# PGTN_daisy1_controls_8cvin_2cvout.net
KiCad netlist of a schematic drawn in EAGLE
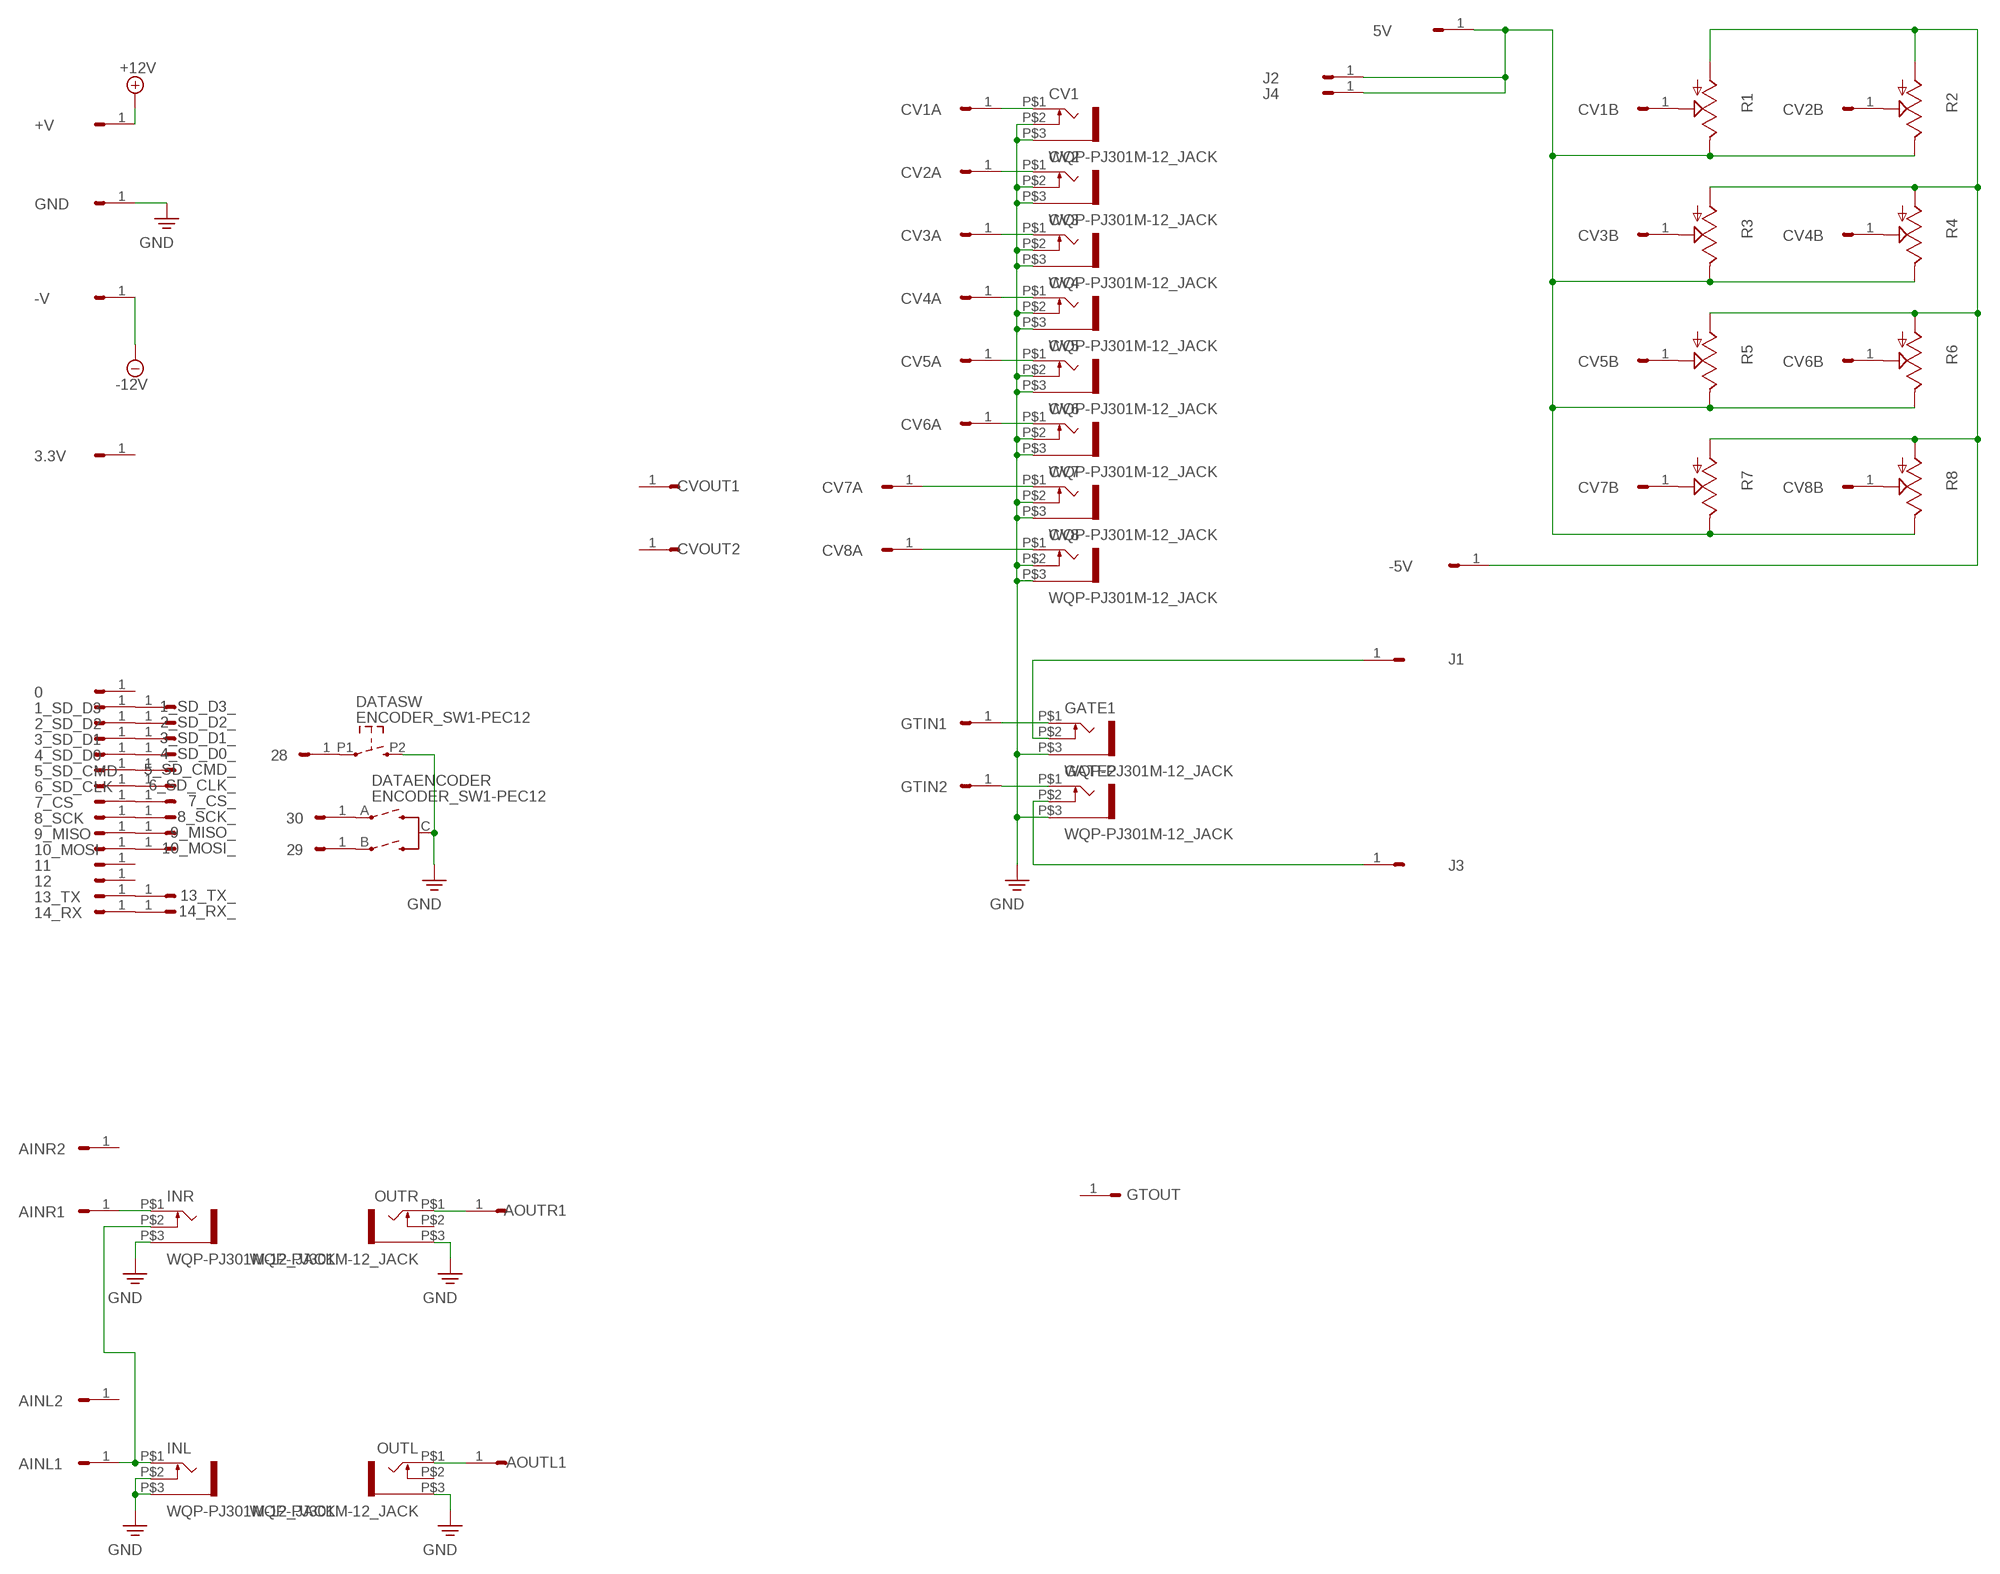
[diagram p0: schematic, sheet 1]

(export (version "E")
  (design (tool "Eeschema 10.0.6"))
  (components
    (comp (ref "+V")
      (value "HEADER/MALE/01")
      (footprint "eagle-import:HEADER_MALE_01")
      (fields (field (name "SPICEPREFIX") "X"))
      (libsource (lib "eagle-import") (part "HEADER/MALE/01"))
    )
    (comp (ref "-5V")
      (value "HEADER/MALE/01")
      (footprint "eagle-import:HEADER_MALE_01")
      (fields (field (name "SPICEPREFIX") "X"))
      (libsource (lib "eagle-import") (part "HEADER/MALE/01"))
    )
    (comp (ref "-V")
      (value "HEADER/MALE/01")
      (footprint "eagle-import:HEADER_MALE_01")
      (fields (field (name "SPICEPREFIX") "X"))
      (libsource (lib "eagle-import") (part "HEADER/MALE/01"))
    )
    (comp (ref "0")
      (value "HEADER/MALE/01")
      (footprint "eagle-import:HEADER_MALE_01")
      (fields (field (name "SPICEPREFIX") "X"))
      (libsource (lib "eagle-import") (part "HEADER/MALE/01"))
    )
    (comp (ref "1_SD_D3")
      (value "HEADER/MALE/01")
      (footprint "eagle-import:HEADER_MALE_01")
      (fields (field (name "SPICEPREFIX") "X"))
      (libsource (lib "eagle-import") (part "HEADER/MALE/01"))
    )
    (comp (ref "1_SD_D3_")
      (value "HEADER/MALE/01")
      (footprint "eagle-import:HEADER_MALE_01")
      (fields (field (name "SPICEPREFIX") "X"))
      (libsource (lib "eagle-import") (part "HEADER/MALE/01"))
    )
    (comp (ref "2_SD_D2")
      (value "HEADER/MALE/01")
      (footprint "eagle-import:HEADER_MALE_01")
      (fields (field (name "SPICEPREFIX") "X"))
      (libsource (lib "eagle-import") (part "HEADER/MALE/01"))
    )
    (comp (ref "2_SD_D2_")
      (value "HEADER/MALE/01")
      (footprint "eagle-import:HEADER_MALE_01")
      (fields (field (name "SPICEPREFIX") "X"))
      (libsource (lib "eagle-import") (part "HEADER/MALE/01"))
    )
    (comp (ref "3.3V")
      (value "HEADER/MALE/01")
      (footprint "eagle-import:HEADER_MALE_01")
      (fields (field (name "SPICEPREFIX") "X"))
      (libsource (lib "eagle-import") (part "HEADER/MALE/01"))
    )
    (comp (ref "3_SD_D1")
      (value "HEADER/MALE/01")
      (footprint "eagle-import:HEADER_MALE_01")
      (fields (field (name "SPICEPREFIX") "X"))
      (libsource (lib "eagle-import") (part "HEADER/MALE/01"))
    )
    (comp (ref "3_SD_D1_")
      (value "HEADER/MALE/01")
      (footprint "eagle-import:HEADER_MALE_01")
      (fields (field (name "SPICEPREFIX") "X"))
      (libsource (lib "eagle-import") (part "HEADER/MALE/01"))
    )
    (comp (ref "4_SD_D0")
      (value "HEADER/MALE/01")
      (footprint "eagle-import:HEADER_MALE_01")
      (fields (field (name "SPICEPREFIX") "X"))
      (libsource (lib "eagle-import") (part "HEADER/MALE/01"))
    )
    (comp (ref "4_SD_D0_")
      (value "HEADER/MALE/01")
      (footprint "eagle-import:HEADER_MALE_01")
      (fields (field (name "SPICEPREFIX") "X"))
      (libsource (lib "eagle-import") (part "HEADER/MALE/01"))
    )
    (comp (ref "5V")
      (value "HEADER/MALE/01")
      (footprint "eagle-import:HEADER_MALE_01")
      (fields (field (name "SPICEPREFIX") "X"))
      (libsource (lib "eagle-import") (part "HEADER/MALE/01"))
    )
    (comp (ref "5_SD_CMD")
      (value "HEADER/MALE/01")
      (footprint "eagle-import:HEADER_MALE_01")
      (fields (field (name "SPICEPREFIX") "X"))
      (libsource (lib "eagle-import") (part "HEADER/MALE/01"))
    )
    (comp (ref "5_SD_CMD_")
      (value "HEADER/MALE/01")
      (footprint "eagle-import:HEADER_MALE_01")
      (fields (field (name "SPICEPREFIX") "X"))
      (libsource (lib "eagle-import") (part "HEADER/MALE/01"))
    )
    (comp (ref "6_SD_CLK")
      (value "HEADER/MALE/01")
      (footprint "eagle-import:HEADER_MALE_01")
      (fields (field (name "SPICEPREFIX") "X"))
      (libsource (lib "eagle-import") (part "HEADER/MALE/01"))
    )
    (comp (ref "6_SD_CLK_")
      (value "HEADER/MALE/01")
      (footprint "eagle-import:HEADER_MALE_01")
      (fields (field (name "SPICEPREFIX") "X"))
      (libsource (lib "eagle-import") (part "HEADER/MALE/01"))
    )
    (comp (ref "7_CS")
      (value "HEADER/MALE/01")
      (footprint "eagle-import:HEADER_MALE_01")
      (fields (field (name "SPICEPREFIX") "X"))
      (libsource (lib "eagle-import") (part "HEADER/MALE/01"))
    )
    (comp (ref "7_CS_")
      (value "HEADER/MALE/01")
      (footprint "eagle-import:HEADER_MALE_01")
      (fields (field (name "SPICEPREFIX") "X"))
      (libsource (lib "eagle-import") (part "HEADER/MALE/01"))
    )
    (comp (ref "8_SCK")
      (value "HEADER/MALE/01")
      (footprint "eagle-import:HEADER_MALE_01")
      (fields (field (name "SPICEPREFIX") "X"))
      (libsource (lib "eagle-import") (part "HEADER/MALE/01"))
    )
    (comp (ref "8_SCK_")
      (value "HEADER/MALE/01")
      (footprint "eagle-import:HEADER_MALE_01")
      (fields (field (name "SPICEPREFIX") "X"))
      (libsource (lib "eagle-import") (part "HEADER/MALE/01"))
    )
    (comp (ref "9_MISO")
      (value "HEADER/MALE/01")
      (footprint "eagle-import:HEADER_MALE_01")
      (fields (field (name "SPICEPREFIX") "X"))
      (libsource (lib "eagle-import") (part "HEADER/MALE/01"))
    )
    (comp (ref "9_MISO_")
      (value "HEADER/MALE/01")
      (footprint "eagle-import:HEADER_MALE_01")
      (fields (field (name "SPICEPREFIX") "X"))
      (libsource (lib "eagle-import") (part "HEADER/MALE/01"))
    )
    (comp (ref "10_MOSI")
      (value "HEADER/MALE/01")
      (footprint "eagle-import:HEADER_MALE_01")
      (fields (field (name "SPICEPREFIX") "X"))
      (libsource (lib "eagle-import") (part "HEADER/MALE/01"))
    )
    (comp (ref "10_MOSI_")
      (value "HEADER/MALE/01")
      (footprint "eagle-import:HEADER_MALE_01")
      (fields (field (name "SPICEPREFIX") "X"))
      (libsource (lib "eagle-import") (part "HEADER/MALE/01"))
    )
    (comp (ref "11")
      (value "HEADER/MALE/01")
      (footprint "eagle-import:HEADER_MALE_01")
      (fields (field (name "SPICEPREFIX") "X"))
      (libsource (lib "eagle-import") (part "HEADER/MALE/01"))
    )
    (comp (ref "12")
      (value "HEADER/MALE/01")
      (footprint "eagle-import:HEADER_MALE_01")
      (fields (field (name "SPICEPREFIX") "X"))
      (libsource (lib "eagle-import") (part "HEADER/MALE/01"))
    )
    (comp (ref "13_TX")
      (value "HEADER/MALE/01")
      (footprint "eagle-import:HEADER_MALE_01")
      (fields (field (name "SPICEPREFIX") "X"))
      (libsource (lib "eagle-import") (part "HEADER/MALE/01"))
    )
    (comp (ref "13_TX_")
      (value "HEADER/MALE/01")
      (footprint "eagle-import:HEADER_MALE_01")
      (fields (field (name "SPICEPREFIX") "X"))
      (libsource (lib "eagle-import") (part "HEADER/MALE/01"))
    )
    (comp (ref "14_RX")
      (value "HEADER/MALE/01")
      (footprint "eagle-import:HEADER_MALE_01")
      (fields (field (name "SPICEPREFIX") "X"))
      (libsource (lib "eagle-import") (part "HEADER/MALE/01"))
    )
    (comp (ref "14_RX_")
      (value "HEADER/MALE/01")
      (footprint "eagle-import:HEADER_MALE_01")
      (fields (field (name "SPICEPREFIX") "X"))
      (libsource (lib "eagle-import") (part "HEADER/MALE/01"))
    )
    (comp (ref "28")
      (value "HEADER/MALE/01")
      (footprint "eagle-import:HEADER_MALE_01")
      (fields (field (name "SPICEPREFIX") "X"))
      (libsource (lib "eagle-import") (part "HEADER/MALE/01"))
    )
    (comp (ref "29")
      (value "HEADER/MALE/01")
      (footprint "eagle-import:HEADER_MALE_01")
      (fields (field (name "SPICEPREFIX") "X"))
      (libsource (lib "eagle-import") (part "HEADER/MALE/01"))
    )
    (comp (ref "30")
      (value "HEADER/MALE/01")
      (footprint "eagle-import:HEADER_MALE_01")
      (fields (field (name "SPICEPREFIX") "X"))
      (libsource (lib "eagle-import") (part "HEADER/MALE/01"))
    )
    (comp (ref "AINL1")
      (value "HEADER/MALE/01")
      (footprint "eagle-import:HEADER_MALE_01")
      (fields (field (name "SPICEPREFIX") "X"))
      (libsource (lib "eagle-import") (part "HEADER/MALE/01"))
    )
    (comp (ref "AINL2")
      (value "HEADER/MALE/01")
      (footprint "eagle-import:HEADER_MALE_01")
      (fields (field (name "SPICEPREFIX") "X"))
      (libsource (lib "eagle-import") (part "HEADER/MALE/01"))
    )
    (comp (ref "AINR1")
      (value "HEADER/MALE/01")
      (footprint "eagle-import:HEADER_MALE_01")
      (fields (field (name "SPICEPREFIX") "X"))
      (libsource (lib "eagle-import") (part "HEADER/MALE/01"))
    )
    (comp (ref "AINR2")
      (value "HEADER/MALE/01")
      (footprint "eagle-import:HEADER_MALE_01")
      (fields (field (name "SPICEPREFIX") "X"))
      (libsource (lib "eagle-import") (part "HEADER/MALE/01"))
    )
    (comp (ref "AOUTL1")
      (value "HEADER/MALE/01")
      (footprint "eagle-import:HEADER_MALE_01")
      (fields (field (name "SPICEPREFIX") "X"))
      (libsource (lib "eagle-import") (part "HEADER/MALE/01"))
    )
    (comp (ref "AOUTR1")
      (value "HEADER/MALE/01")
      (footprint "eagle-import:HEADER_MALE_01")
      (fields (field (name "SPICEPREFIX") "X"))
      (libsource (lib "eagle-import") (part "HEADER/MALE/01"))
    )
    (comp (ref "CV1")
      (value "WQP-PJ301M-12_JACK")
      (footprint "eagle-import:WQP-PJ301M-12_JACK")
      (libsource (lib "eagle-import") (part "WQP-PJ301M-12_JACK"))
    )
    (comp (ref "CV1A")
      (value "HEADER/MALE/01")
      (footprint "eagle-import:HEADER_MALE_01")
      (fields (field (name "SPICEPREFIX") "X"))
      (libsource (lib "eagle-import") (part "HEADER/MALE/01"))
    )
    (comp (ref "CV1B")
      (value "HEADER/MALE/01")
      (footprint "eagle-import:HEADER_MALE_01")
      (fields (field (name "SPICEPREFIX") "X"))
      (libsource (lib "eagle-import") (part "HEADER/MALE/01"))
    )
    (comp (ref "CV2")
      (value "WQP-PJ301M-12_JACK")
      (footprint "eagle-import:WQP-PJ301M-12_JACK")
      (libsource (lib "eagle-import") (part "WQP-PJ301M-12_JACK"))
    )
    (comp (ref "CV2A")
      (value "HEADER/MALE/01")
      (footprint "eagle-import:HEADER_MALE_01")
      (fields (field (name "SPICEPREFIX") "X"))
      (libsource (lib "eagle-import") (part "HEADER/MALE/01"))
    )
    (comp (ref "CV2B")
      (value "HEADER/MALE/01")
      (footprint "eagle-import:HEADER_MALE_01")
      (fields (field (name "SPICEPREFIX") "X"))
      (libsource (lib "eagle-import") (part "HEADER/MALE/01"))
    )
    (comp (ref "CV3")
      (value "WQP-PJ301M-12_JACK")
      (footprint "eagle-import:WQP-PJ301M-12_JACK")
      (libsource (lib "eagle-import") (part "WQP-PJ301M-12_JACK"))
    )
    (comp (ref "CV3A")
      (value "HEADER/MALE/01")
      (footprint "eagle-import:HEADER_MALE_01")
      (fields (field (name "SPICEPREFIX") "X"))
      (libsource (lib "eagle-import") (part "HEADER/MALE/01"))
    )
    (comp (ref "CV3B")
      (value "HEADER/MALE/01")
      (footprint "eagle-import:HEADER_MALE_01")
      (fields (field (name "SPICEPREFIX") "X"))
      (libsource (lib "eagle-import") (part "HEADER/MALE/01"))
    )
    (comp (ref "CV4")
      (value "WQP-PJ301M-12_JACK")
      (footprint "eagle-import:WQP-PJ301M-12_JACK")
      (libsource (lib "eagle-import") (part "WQP-PJ301M-12_JACK"))
    )
    (comp (ref "CV4A")
      (value "HEADER/MALE/01")
      (footprint "eagle-import:HEADER_MALE_01")
      (fields (field (name "SPICEPREFIX") "X"))
      (libsource (lib "eagle-import") (part "HEADER/MALE/01"))
    )
    (comp (ref "CV4B")
      (value "HEADER/MALE/01")
      (footprint "eagle-import:HEADER_MALE_01")
      (fields (field (name "SPICEPREFIX") "X"))
      (libsource (lib "eagle-import") (part "HEADER/MALE/01"))
    )
    (comp (ref "CV5")
      (value "WQP-PJ301M-12_JACK")
      (footprint "eagle-import:WQP-PJ301M-12_JACK")
      (libsource (lib "eagle-import") (part "WQP-PJ301M-12_JACK"))
    )
    (comp (ref "CV5A")
      (value "HEADER/MALE/01")
      (footprint "eagle-import:HEADER_MALE_01")
      (fields (field (name "SPICEPREFIX") "X"))
      (libsource (lib "eagle-import") (part "HEADER/MALE/01"))
    )
    (comp (ref "CV5B")
      (value "HEADER/MALE/01")
      (footprint "eagle-import:HEADER_MALE_01")
      (fields (field (name "SPICEPREFIX") "X"))
      (libsource (lib "eagle-import") (part "HEADER/MALE/01"))
    )
    (comp (ref "CV6")
      (value "WQP-PJ301M-12_JACK")
      (footprint "eagle-import:WQP-PJ301M-12_JACK")
      (libsource (lib "eagle-import") (part "WQP-PJ301M-12_JACK"))
    )
    (comp (ref "CV6A")
      (value "HEADER/MALE/01")
      (footprint "eagle-import:HEADER_MALE_01")
      (fields (field (name "SPICEPREFIX") "X"))
      (libsource (lib "eagle-import") (part "HEADER/MALE/01"))
    )
    (comp (ref "CV6B")
      (value "HEADER/MALE/01")
      (footprint "eagle-import:HEADER_MALE_01")
      (fields (field (name "SPICEPREFIX") "X"))
      (libsource (lib "eagle-import") (part "HEADER/MALE/01"))
    )
    (comp (ref "CV7")
      (value "WQP-PJ301M-12_JACK")
      (footprint "eagle-import:WQP-PJ301M-12_JACK")
      (libsource (lib "eagle-import") (part "WQP-PJ301M-12_JACK"))
    )
    (comp (ref "CV7A")
      (value "HEADER/MALE/01")
      (footprint "eagle-import:HEADER_MALE_01")
      (fields (field (name "SPICEPREFIX") "X"))
      (libsource (lib "eagle-import") (part "HEADER/MALE/01"))
    )
    (comp (ref "CV7B")
      (value "HEADER/MALE/01")
      (footprint "eagle-import:HEADER_MALE_01")
      (fields (field (name "SPICEPREFIX") "X"))
      (libsource (lib "eagle-import") (part "HEADER/MALE/01"))
    )
    (comp (ref "CV8")
      (value "WQP-PJ301M-12_JACK")
      (footprint "eagle-import:WQP-PJ301M-12_JACK")
      (libsource (lib "eagle-import") (part "WQP-PJ301M-12_JACK"))
    )
    (comp (ref "CV8A")
      (value "HEADER/MALE/01")
      (footprint "eagle-import:HEADER_MALE_01")
      (fields (field (name "SPICEPREFIX") "X"))
      (libsource (lib "eagle-import") (part "HEADER/MALE/01"))
    )
    (comp (ref "CV8B")
      (value "HEADER/MALE/01")
      (footprint "eagle-import:HEADER_MALE_01")
      (fields (field (name "SPICEPREFIX") "X"))
      (libsource (lib "eagle-import") (part "HEADER/MALE/01"))
    )
    (comp (ref "CVOUT1")
      (value "HEADER/MALE/01")
      (footprint "eagle-import:HEADER_MALE_01")
      (fields (field (name "SPICEPREFIX") "X"))
      (libsource (lib "eagle-import") (part "HEADER/MALE/01"))
    )
    (comp (ref "CVOUT2")
      (value "HEADER/MALE/01")
      (footprint "eagle-import:HEADER_MALE_01")
      (fields (field (name "SPICEPREFIX") "X"))
      (libsource (lib "eagle-import") (part "HEADER/MALE/01"))
    )
    (comp (ref "DATA")
      (value "ENCODER_SW1-PEC12")
      (footprint "eagle-import:PEC12_INCREMENTAL_ENCODER")
      (libsource (lib "eagle-import") (part "ENCODER_SW1-PEC12"))
    )
    (comp (ref "GATE1")
      (value "WQP-PJ301M-12_JACK")
      (footprint "eagle-import:WQP-PJ301M-12_JACK")
      (libsource (lib "eagle-import") (part "WQP-PJ301M-12_JACK"))
    )
    (comp (ref "GATE2")
      (value "WQP-PJ301M-12_JACK")
      (footprint "eagle-import:WQP-PJ301M-12_JACK")
      (libsource (lib "eagle-import") (part "WQP-PJ301M-12_JACK"))
    )
    (comp (ref "GND")
      (value "HEADER/MALE/01")
      (footprint "eagle-import:HEADER_MALE_01")
      (fields (field (name "SPICEPREFIX") "X"))
      (libsource (lib "eagle-import") (part "HEADER/MALE/01"))
    )
    (comp (ref "GTIN1")
      (value "HEADER/MALE/01")
      (footprint "eagle-import:HEADER_MALE_01")
      (fields (field (name "SPICEPREFIX") "X"))
      (libsource (lib "eagle-import") (part "HEADER/MALE/01"))
    )
    (comp (ref "GTIN2")
      (value "HEADER/MALE/01")
      (footprint "eagle-import:HEADER_MALE_01")
      (fields (field (name "SPICEPREFIX") "X"))
      (libsource (lib "eagle-import") (part "HEADER/MALE/01"))
    )
    (comp (ref "GTOUT")
      (value "HEADER/MALE/01")
      (footprint "eagle-import:HEADER_MALE_01")
      (fields (field (name "SPICEPREFIX") "X"))
      (libsource (lib "eagle-import") (part "HEADER/MALE/01"))
    )
    (comp (ref "INL")
      (value "WQP-PJ301M-12_JACK")
      (footprint "eagle-import:WQP-PJ301M-12_JACK")
      (libsource (lib "eagle-import") (part "WQP-PJ301M-12_JACK"))
    )
    (comp (ref "INR")
      (value "WQP-PJ301M-12_JACK")
      (footprint "eagle-import:WQP-PJ301M-12_JACK")
      (libsource (lib "eagle-import") (part "WQP-PJ301M-12_JACK"))
    )
    (comp (ref "J1")
      (value "HEADER/MALE/01")
      (footprint "eagle-import:HEADER_MALE_01")
      (fields (field (name "SPICEPREFIX") "X"))
      (libsource (lib "eagle-import") (part "HEADER/MALE/01"))
    )
    (comp (ref "J2")
      (value "HEADER/MALE/01")
      (footprint "eagle-import:HEADER_MALE_01")
      (fields (field (name "SPICEPREFIX") "X"))
      (libsource (lib "eagle-import") (part "HEADER/MALE/01"))
    )
    (comp (ref "J3")
      (value "HEADER/MALE/01")
      (footprint "eagle-import:HEADER_MALE_01")
      (fields (field (name "SPICEPREFIX") "X"))
      (libsource (lib "eagle-import") (part "HEADER/MALE/01"))
    )
    (comp (ref "J4")
      (value "HEADER/MALE/01")
      (footprint "eagle-import:HEADER_MALE_01")
      (fields (field (name "SPICEPREFIX") "X"))
      (libsource (lib "eagle-import") (part "HEADER/MALE/01"))
    )
    (comp (ref "OUTL")
      (value "WQP-PJ301M-12_JACK")
      (footprint "eagle-import:WQP-PJ301M-12_JACK")
      (libsource (lib "eagle-import") (part "WQP-PJ301M-12_JACK"))
    )
    (comp (ref "OUTR")
      (value "WQP-PJ301M-12_JACK")
      (footprint "eagle-import:WQP-PJ301M-12_JACK")
      (libsource (lib "eagle-import") (part "WQP-PJ301M-12_JACK"))
    )
    (comp (ref "R1")
      (value "9MM_SNAP-IN_POT_")
      (footprint "eagle-import:9MM_SNAP-IN_POT")
      (libsource (lib "eagle-import") (part "9MM_SNAP-IN_POT_"))
    )
    (comp (ref "R2")
      (value "9MM_SNAP-IN_POT_")
      (footprint "eagle-import:9MM_SNAP-IN_POT")
      (libsource (lib "eagle-import") (part "9MM_SNAP-IN_POT_"))
    )
    (comp (ref "R3")
      (value "9MM_SNAP-IN_POT_")
      (footprint "eagle-import:9MM_SNAP-IN_POT")
      (libsource (lib "eagle-import") (part "9MM_SNAP-IN_POT_"))
    )
    (comp (ref "R4")
      (value "9MM_SNAP-IN_POT_")
      (footprint "eagle-import:9MM_SNAP-IN_POT")
      (libsource (lib "eagle-import") (part "9MM_SNAP-IN_POT_"))
    )
    (comp (ref "R5")
      (value "9MM_SNAP-IN_POT_")
      (footprint "eagle-import:9MM_SNAP-IN_POT")
      (libsource (lib "eagle-import") (part "9MM_SNAP-IN_POT_"))
    )
    (comp (ref "R6")
      (value "9MM_SNAP-IN_POT_")
      (footprint "eagle-import:9MM_SNAP-IN_POT")
      (libsource (lib "eagle-import") (part "9MM_SNAP-IN_POT_"))
    )
    (comp (ref "R7")
      (value "9MM_SNAP-IN_POT_")
      (footprint "eagle-import:9MM_SNAP-IN_POT")
      (libsource (lib "eagle-import") (part "9MM_SNAP-IN_POT_"))
    )
    (comp (ref "R8")
      (value "9MM_SNAP-IN_POT_")
      (footprint "eagle-import:9MM_SNAP-IN_POT")
      (libsource (lib "eagle-import") (part "9MM_SNAP-IN_POT_"))
    )
  )
  (nets
    (net (code "1") (name "+12V") (class "Default")
      (node (ref "+V") (pin "1") (pinfunction "3_1") (pintype "passive"))
    )
    (net (code "2") (name "-12V") (class "Default")
      (node (ref "-V") (pin "1") (pinfunction "3_1") (pintype "passive"))
    )
    (net (code "3") (name "GND") (class "Default")
      (node (ref "CV1") (pin "P$2") (pinfunction "3_P$2") (pintype "passive"))
      (node (ref "CV1") (pin "P$3") (pinfunction "1_P$3") (pintype "passive"))
      (node (ref "CV2") (pin "P$2") (pinfunction "3_P$2") (pintype "passive"))
      (node (ref "CV2") (pin "P$3") (pinfunction "1_P$3") (pintype "passive"))
      (node (ref "CV3") (pin "P$2") (pinfunction "3_P$2") (pintype "passive"))
      (node (ref "CV3") (pin "P$3") (pinfunction "1_P$3") (pintype "passive"))
      (node (ref "CV4") (pin "P$2") (pinfunction "3_P$2") (pintype "passive"))
      (node (ref "CV4") (pin "P$3") (pinfunction "1_P$3") (pintype "passive"))
      (node (ref "CV5") (pin "P$2") (pinfunction "3_P$2") (pintype "passive"))
      (node (ref "CV5") (pin "P$3") (pinfunction "1_P$3") (pintype "passive"))
      (node (ref "CV6") (pin "P$2") (pinfunction "3_P$2") (pintype "passive"))
      (node (ref "CV6") (pin "P$3") (pinfunction "1_P$3") (pintype "passive"))
      (node (ref "CV7") (pin "P$2") (pinfunction "3_P$2") (pintype "passive"))
      (node (ref "CV7") (pin "P$3") (pinfunction "1_P$3") (pintype "passive"))
      (node (ref "CV8") (pin "P$2") (pinfunction "3_P$2") (pintype "passive"))
      (node (ref "CV8") (pin "P$3") (pinfunction "1_P$3") (pintype "passive"))
      (node (ref "DATA") (pin "C") (pinfunction "C_C") (pintype "passive"))
      (node (ref "DATA") (pin "P2") (pinfunction "2_P2") (pintype "passive"))
      (node (ref "GATE1") (pin "P$3") (pinfunction "1_P$3") (pintype "passive"))
      (node (ref "GATE2") (pin "P$3") (pinfunction "1_P$3") (pintype "passive"))
      (node (ref "GND") (pin "1") (pinfunction "3_1") (pintype "passive"))
      (node (ref "INL") (pin "P$2") (pinfunction "3_P$2") (pintype "passive"))
      (node (ref "INL") (pin "P$3") (pinfunction "1_P$3") (pintype "passive"))
      (node (ref "INR") (pin "P$3") (pinfunction "1_P$3") (pintype "passive"))
      (node (ref "OUTL") (pin "P$3") (pinfunction "1_P$3") (pintype "passive"))
      (node (ref "OUTR") (pin "P$3") (pinfunction "1_P$3") (pintype "passive"))
    )
    (net (code "4") (name "Net-(-5V-3)") (class "Default")
      (node (ref "-5V") (pin "1") (pinfunction "3_1") (pintype "passive"))
      (node (ref "R1") (pin "1") (pinfunction "A_1") (pintype "passive"))
      (node (ref "R2") (pin "1") (pinfunction "A_1") (pintype "passive"))
      (node (ref "R3") (pin "1") (pinfunction "A_1") (pintype "passive"))
      (node (ref "R4") (pin "1") (pinfunction "A_1") (pintype "passive"))
      (node (ref "R5") (pin "1") (pinfunction "A_1") (pintype "passive"))
      (node (ref "R6") (pin "1") (pinfunction "A_1") (pintype "passive"))
      (node (ref "R7") (pin "1") (pinfunction "A_1") (pintype "passive"))
      (node (ref "R8") (pin "1") (pinfunction "A_1") (pintype "passive"))
    )
    (net (code "5") (name "Net-(1_SD_D3-3)") (class "Default")
      (node (ref "1_SD_D3") (pin "1") (pinfunction "3_1") (pintype "passive"))
      (node (ref "1_SD_D3_") (pin "1") (pinfunction "3_1") (pintype "passive"))
    )
    (net (code "6") (name "Net-(2_SD_D2-3)") (class "Default")
      (node (ref "2_SD_D2") (pin "1") (pinfunction "3_1") (pintype "passive"))
      (node (ref "2_SD_D2_") (pin "1") (pinfunction "3_1") (pintype "passive"))
    )
    (net (code "7") (name "Net-(3_SD_D1-3)") (class "Default")
      (node (ref "3_SD_D1") (pin "1") (pinfunction "3_1") (pintype "passive"))
      (node (ref "3_SD_D1_") (pin "1") (pinfunction "3_1") (pintype "passive"))
    )
    (net (code "8") (name "Net-(4_SD_D0-3)") (class "Default")
      (node (ref "4_SD_D0") (pin "1") (pinfunction "3_1") (pintype "passive"))
      (node (ref "4_SD_D0_") (pin "1") (pinfunction "3_1") (pintype "passive"))
    )
    (net (code "9") (name "Net-(5V-3)") (class "Default")
      (node (ref "5V") (pin "1") (pinfunction "3_1") (pintype "passive"))
      (node (ref "J2") (pin "1") (pinfunction "3_1") (pintype "passive"))
      (node (ref "J4") (pin "1") (pinfunction "3_1") (pintype "passive"))
      (node (ref "R1") (pin "3") (pinfunction "E_3") (pintype "passive"))
      (node (ref "R2") (pin "3") (pinfunction "E_3") (pintype "passive"))
      (node (ref "R3") (pin "3") (pinfunction "E_3") (pintype "passive"))
      (node (ref "R4") (pin "3") (pinfunction "E_3") (pintype "passive"))
      (node (ref "R5") (pin "3") (pinfunction "E_3") (pintype "passive"))
      (node (ref "R6") (pin "3") (pinfunction "E_3") (pintype "passive"))
      (node (ref "R7") (pin "3") (pinfunction "E_3") (pintype "passive"))
      (node (ref "R8") (pin "3") (pinfunction "E_3") (pintype "passive"))
    )
    (net (code "10") (name "Net-(5_SD_CMD-3)") (class "Default")
      (node (ref "5_SD_CMD") (pin "1") (pinfunction "3_1") (pintype "passive"))
      (node (ref "5_SD_CMD_") (pin "1") (pinfunction "3_1") (pintype "passive"))
    )
    (net (code "11") (name "Net-(6_SD_CLK-3)") (class "Default")
      (node (ref "6_SD_CLK") (pin "1") (pinfunction "3_1") (pintype "passive"))
      (node (ref "6_SD_CLK_") (pin "1") (pinfunction "3_1") (pintype "passive"))
    )
    (net (code "12") (name "Net-(7_CS-3)") (class "Default")
      (node (ref "7_CS") (pin "1") (pinfunction "3_1") (pintype "passive"))
      (node (ref "7_CS_") (pin "1") (pinfunction "3_1") (pintype "passive"))
    )
    (net (code "13") (name "Net-(8_SCK-3)") (class "Default")
      (node (ref "8_SCK") (pin "1") (pinfunction "3_1") (pintype "passive"))
      (node (ref "8_SCK_") (pin "1") (pinfunction "3_1") (pintype "passive"))
    )
    (net (code "14") (name "Net-(9_MISO-3)") (class "Default")
      (node (ref "9_MISO") (pin "1") (pinfunction "3_1") (pintype "passive"))
      (node (ref "9_MISO_") (pin "1") (pinfunction "3_1") (pintype "passive"))
    )
    (net (code "15") (name "Net-(10_MOSI-3)") (class "Default")
      (node (ref "10_MOSI") (pin "1") (pinfunction "3_1") (pintype "passive"))
      (node (ref "10_MOSI_") (pin "1") (pinfunction "3_1") (pintype "passive"))
    )
    (net (code "16") (name "Net-(13_TX-3)") (class "Default")
      (node (ref "13_TX") (pin "1") (pinfunction "3_1") (pintype "passive"))
      (node (ref "13_TX_") (pin "1") (pinfunction "3_1") (pintype "passive"))
    )
    (net (code "17") (name "Net-(14_RX-3)") (class "Default")
      (node (ref "14_RX") (pin "1") (pinfunction "3_1") (pintype "passive"))
      (node (ref "14_RX_") (pin "1") (pinfunction "3_1") (pintype "passive"))
    )
    (net (code "18") (name "Net-(28-3)") (class "Default")
      (node (ref "28") (pin "1") (pinfunction "3_1") (pintype "passive"))
      (node (ref "DATA") (pin "P1") (pinfunction "1_P1") (pintype "passive"))
    )
    (net (code "19") (name "Net-(29-3)") (class "Default")
      (node (ref "29") (pin "1") (pinfunction "3_1") (pintype "passive"))
      (node (ref "DATA") (pin "B") (pinfunction "B_B") (pintype "passive"))
    )
    (net (code "20") (name "Net-(30-3)") (class "Default")
      (node (ref "30") (pin "1") (pinfunction "3_1") (pintype "passive"))
      (node (ref "DATA") (pin "A") (pinfunction "A_A") (pintype "passive"))
    )
    (net (code "21") (name "Net-(AINL1-3)") (class "Default")
      (node (ref "AINL1") (pin "1") (pinfunction "3_1") (pintype "passive"))
      (node (ref "INL") (pin "P$1") (pinfunction "2_P$1") (pintype "passive"))
      (node (ref "INR") (pin "P$2") (pinfunction "3_P$2") (pintype "passive"))
    )
    (net (code "22") (name "Net-(AINR1-3)") (class "Default")
      (node (ref "AINR1") (pin "1") (pinfunction "3_1") (pintype "passive"))
      (node (ref "INR") (pin "P$1") (pinfunction "2_P$1") (pintype "passive"))
    )
    (net (code "23") (name "Net-(AOUTL1-3)") (class "Default")
      (node (ref "AOUTL1") (pin "1") (pinfunction "3_1") (pintype "passive"))
      (node (ref "OUTL") (pin "P$1") (pinfunction "2_P$1") (pintype "passive"))
    )
    (net (code "24") (name "Net-(AOUTR1-3)") (class "Default")
      (node (ref "AOUTR1") (pin "1") (pinfunction "3_1") (pintype "passive"))
      (node (ref "OUTR") (pin "P$1") (pinfunction "2_P$1") (pintype "passive"))
    )
    (net (code "25") (name "Net-(CV1-2)") (class "Default")
      (node (ref "CV1") (pin "P$1") (pinfunction "2_P$1") (pintype "passive"))
      (node (ref "CV1A") (pin "1") (pinfunction "3_1") (pintype "passive"))
    )
    (net (code "26") (name "Net-(CV1B-3)") (class "Default")
      (node (ref "CV1B") (pin "1") (pinfunction "3_1") (pintype "passive"))
      (node (ref "R1") (pin "2") (pinfunction "S_2") (pintype "passive"))
    )
    (net (code "27") (name "Net-(CV2-2)") (class "Default")
      (node (ref "CV2") (pin "P$1") (pinfunction "2_P$1") (pintype "passive"))
      (node (ref "CV2A") (pin "1") (pinfunction "3_1") (pintype "passive"))
    )
    (net (code "28") (name "Net-(CV2B-3)") (class "Default")
      (node (ref "CV2B") (pin "1") (pinfunction "3_1") (pintype "passive"))
      (node (ref "R2") (pin "2") (pinfunction "S_2") (pintype "passive"))
    )
    (net (code "29") (name "Net-(CV3-2)") (class "Default")
      (node (ref "CV3") (pin "P$1") (pinfunction "2_P$1") (pintype "passive"))
      (node (ref "CV3A") (pin "1") (pinfunction "3_1") (pintype "passive"))
    )
    (net (code "30") (name "Net-(CV3B-3)") (class "Default")
      (node (ref "CV3B") (pin "1") (pinfunction "3_1") (pintype "passive"))
      (node (ref "R3") (pin "2") (pinfunction "S_2") (pintype "passive"))
    )
    (net (code "31") (name "Net-(CV4-2)") (class "Default")
      (node (ref "CV4") (pin "P$1") (pinfunction "2_P$1") (pintype "passive"))
      (node (ref "CV4A") (pin "1") (pinfunction "3_1") (pintype "passive"))
    )
    (net (code "32") (name "Net-(CV4B-3)") (class "Default")
      (node (ref "CV4B") (pin "1") (pinfunction "3_1") (pintype "passive"))
      (node (ref "R4") (pin "2") (pinfunction "S_2") (pintype "passive"))
    )
    (net (code "33") (name "Net-(CV5-2)") (class "Default")
      (node (ref "CV5") (pin "P$1") (pinfunction "2_P$1") (pintype "passive"))
      (node (ref "CV5A") (pin "1") (pinfunction "3_1") (pintype "passive"))
    )
    (net (code "34") (name "Net-(CV5B-3)") (class "Default")
      (node (ref "CV5B") (pin "1") (pinfunction "3_1") (pintype "passive"))
      (node (ref "R5") (pin "2") (pinfunction "S_2") (pintype "passive"))
    )
    (net (code "35") (name "Net-(CV6-2)") (class "Default")
      (node (ref "CV6") (pin "P$1") (pinfunction "2_P$1") (pintype "passive"))
      (node (ref "CV6A") (pin "1") (pinfunction "3_1") (pintype "passive"))
    )
    (net (code "36") (name "Net-(CV6B-3)") (class "Default")
      (node (ref "CV6B") (pin "1") (pinfunction "3_1") (pintype "passive"))
      (node (ref "R6") (pin "2") (pinfunction "S_2") (pintype "passive"))
    )
    (net (code "37") (name "Net-(CV7-2)") (class "Default")
      (node (ref "CV7") (pin "P$1") (pinfunction "2_P$1") (pintype "passive"))
      (node (ref "CV7A") (pin "1") (pinfunction "3_1") (pintype "passive"))
    )
    (net (code "38") (name "Net-(CV7B-3)") (class "Default")
      (node (ref "CV7B") (pin "1") (pinfunction "3_1") (pintype "passive"))
      (node (ref "R7") (pin "2") (pinfunction "S_2") (pintype "passive"))
    )
    (net (code "39") (name "Net-(CV8-2)") (class "Default")
      (node (ref "CV8") (pin "P$1") (pinfunction "2_P$1") (pintype "passive"))
      (node (ref "CV8A") (pin "1") (pinfunction "3_1") (pintype "passive"))
    )
    (net (code "40") (name "Net-(CV8B-3)") (class "Default")
      (node (ref "CV8B") (pin "1") (pinfunction "3_1") (pintype "passive"))
      (node (ref "R8") (pin "2") (pinfunction "S_2") (pintype "passive"))
    )
    (net (code "41") (name "Net-(GATE1-2)") (class "Default")
      (node (ref "GATE1") (pin "P$1") (pinfunction "2_P$1") (pintype "passive"))
      (node (ref "GTIN1") (pin "1") (pinfunction "3_1") (pintype "passive"))
    )
    (net (code "42") (name "Net-(GATE1-3)") (class "Default")
      (node (ref "GATE1") (pin "P$2") (pinfunction "3_P$2") (pintype "passive"))
      (node (ref "J1") (pin "1") (pinfunction "3_1") (pintype "passive"))
    )
    (net (code "43") (name "Net-(GATE2-2)") (class "Default")
      (node (ref "GATE2") (pin "P$1") (pinfunction "2_P$1") (pintype "passive"))
      (node (ref "GTIN2") (pin "1") (pinfunction "3_1") (pintype "passive"))
    )
    (net (code "44") (name "Net-(GATE2-3)") (class "Default")
      (node (ref "GATE2") (pin "P$2") (pinfunction "3_P$2") (pintype "passive"))
      (node (ref "J3") (pin "1") (pinfunction "3_1") (pintype "passive"))
    )
    (net (code "45") (name "unconnected-(0-3-Pad1)") (class "Default")
      (node (ref "0") (pin "1") (pinfunction "3_1") (pintype "passive"))
    )
    (net (code "46") (name "unconnected-(3.3V-3-Pad1)") (class "Default")
      (node (ref "3.3V") (pin "1") (pinfunction "3_1") (pintype "passive"))
    )
    (net (code "47") (name "unconnected-(11-3-Pad1)") (class "Default")
      (node (ref "11") (pin "1") (pinfunction "3_1") (pintype "passive"))
    )
    (net (code "48") (name "unconnected-(12-3-Pad1)") (class "Default")
      (node (ref "12") (pin "1") (pinfunction "3_1") (pintype "passive"))
    )
    (net (code "49") (name "unconnected-(AINL2-3-Pad1)") (class "Default")
      (node (ref "AINL2") (pin "1") (pinfunction "3_1") (pintype "passive"))
    )
    (net (code "50") (name "unconnected-(AINR2-3-Pad1)") (class "Default")
      (node (ref "AINR2") (pin "1") (pinfunction "3_1") (pintype "passive"))
    )
    (net (code "51") (name "unconnected-(CVOUT1-3-Pad1)") (class "Default")
      (node (ref "CVOUT1") (pin "1") (pinfunction "3_1") (pintype "passive"))
    )
    (net (code "52") (name "unconnected-(CVOUT2-3-Pad1)") (class "Default")
      (node (ref "CVOUT2") (pin "1") (pinfunction "3_1") (pintype "passive"))
    )
    (net (code "53") (name "unconnected-(GTOUT-3-Pad1)") (class "Default")
      (node (ref "GTOUT") (pin "1") (pinfunction "3_1") (pintype "passive"))
    )
    (net (code "54") (name "unconnected-(OUTL-3-PadP$2)") (class "Default")
      (node (ref "OUTL") (pin "P$2") (pinfunction "3_P$2") (pintype "passive"))
    )
    (net (code "55") (name "unconnected-(OUTR-3-PadP$2)") (class "Default")
      (node (ref "OUTR") (pin "P$2") (pinfunction "3_P$2") (pintype "passive"))
    )
  )
)
